# AskelmoottoriV3.net
KiCad netlist of a schematic drawn in EAGLE
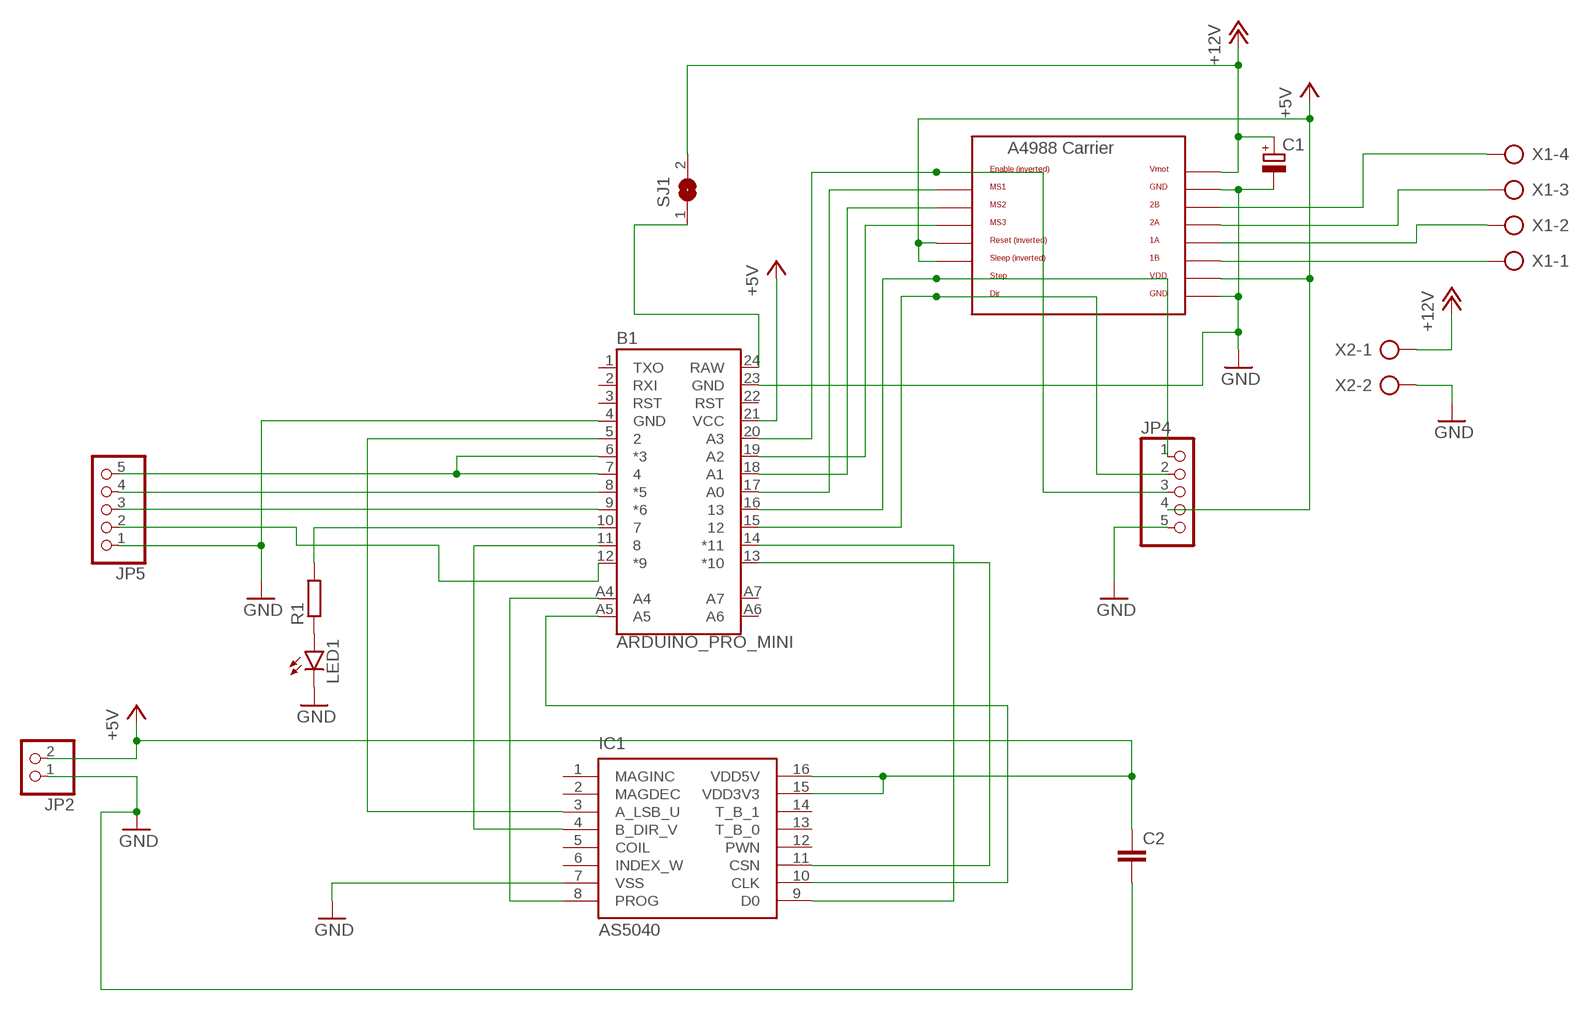
[diagram p0: schematic, sheet 1]

(export (version "E")
  (design (tool "Eeschema 10.0.6"))
  (components
    (comp (ref "B1")
      (value "ARDUINO_PRO_MINI")
      (footprint "eagle-import:ARDUINO_PRO_MINI")
      (libsource (lib "eagle-import") (part "ARDUINO_PRO_MINI"))
    )
    (comp (ref "C1")
      (value "CPOL-EUE5-8.5")
      (footprint "eagle-import:E5-8,5")
      (libsource (lib "eagle-import") (part "CPOL-EUE5-8.5"))
    )
    (comp (ref "C2")
      (value "C-EU025-030X050")
      (footprint "eagle-import:C025-030X050")
      (libsource (lib "eagle-import") (part "C-EU025-030X050"))
    )
    (comp (ref "IC1")
      (value "AS5040")
      (footprint "eagle-import:SSOP16")
      (fields (field (name "MPN") "AS5040ASSU"))
      (libsource (lib "eagle-import") (part "AS5040"))
    )
    (comp (ref "JP2")
      (value "PINHD-1X2")
      (footprint "eagle-import:1X02")
      (libsource (lib "eagle-import") (part "PINHD-1X2"))
    )
    (comp (ref "JP4")
      (value "PINHD-1X5")
      (footprint "eagle-import:1X05")
      (libsource (lib "eagle-import") (part "PINHD-1X5"))
    )
    (comp (ref "JP5")
      (value "PINHD-1X5")
      (footprint "eagle-import:1X05")
      (libsource (lib "eagle-import") (part "PINHD-1X5"))
    )
    (comp (ref "LED1")
      (value "LED3MM")
      (footprint "eagle-import:LED3MM")
      (libsource (lib "eagle-import") (part "LED3MM"))
    )
    (comp (ref "R1")
      (value "R-EU_0207/10")
      (footprint "eagle-import:0207_10")
      (libsource (lib "eagle-import") (part "R-EU_0207/10"))
    )
    (comp (ref "SJ1") (value "SJ") (footprint "eagle-import:SJ") (libsource (lib "eagle-import") (part "SJ")))
    (comp (ref "U$1")
      (value "A4988BREAKOUT")
      (footprint "eagle-import:A4988BREAKOUT")
      (libsource (lib "eagle-import") (part "A4988BREAKOUT"))
    )
    (comp (ref "X1")
      (value "AK300/4")
      (footprint "eagle-import:AK300_4")
      (libsource (lib "eagle-import") (part "AK300/4"))
    )
    (comp (ref "X2")
      (value "AK300/2")
      (footprint "eagle-import:AK300_2")
      (libsource (lib "eagle-import") (part "AK300/2"))
    )
  )
  (nets
    (net (code "1") (name "+5V") (class "Default")
      (node (ref "B1") (pin "21") (pinfunction "VCC_21") (pintype "power_in"))
      (node (ref "C2") (pin "1") (pinfunction "1_1") (pintype "passive"))
      (node (ref "IC1") (pin "15") (pinfunction "VDD3V3_15") (pintype "passive"))
      (node (ref "IC1") (pin "16") (pinfunction "VDD5V_16") (pintype "passive"))
      (node (ref "JP2") (pin "2") (pinfunction "2_2") (pintype "passive"))
      (node (ref "JP4") (pin "4") (pinfunction "4_4") (pintype "passive"))
      (node (ref "U$1") (pin "RST") (pinfunction "RST_RST") (pintype "input"))
      (node (ref "U$1") (pin "SLP") (pinfunction "SLEEP_SLP") (pintype "input"))
      (node (ref "U$1") (pin "VDD") (pinfunction "VDD_VDD") (pintype "power_in"))
    )
    (net (code "2") (name "+12V") (class "Default")
      (node (ref "C1") (pin "+") (pinfunction "+_+") (pintype "passive"))
      (node (ref "SJ1") (pin "2") (pinfunction "2_2") (pintype "passive"))
      (node (ref "U$1") (pin "VMOT") (pinfunction "VMOT_VMOT") (pintype "power_in"))
      (node (ref "X2") (pin "1") (pinfunction "KL_1") (pintype "passive"))
    )
    (net (code "3") (name "GND") (class "Default")
      (node (ref "B1") (pin "23") (pinfunction "GND_23") (pintype "power_in"))
      (node (ref "B1") (pin "4") (pinfunction "GND_4") (pintype "power_in"))
      (node (ref "C1") (pin "-") (pinfunction "-_-") (pintype "passive"))
      (node (ref "C2") (pin "2") (pinfunction "2_2") (pintype "passive"))
      (node (ref "IC1") (pin "7") (pinfunction "VSS_7") (pintype "passive"))
      (node (ref "JP2") (pin "1") (pinfunction "1_1") (pintype "passive"))
      (node (ref "JP4") (pin "5") (pinfunction "5_5") (pintype "passive"))
      (node (ref "JP5") (pin "1") (pinfunction "1_1") (pintype "passive"))
      (node (ref "LED1") (pin "K") (pinfunction "C_K") (pintype "passive"))
      (node (ref "U$1") (pin "GND") (pinfunction "GND_GND") (pintype "power_in"))
      (node (ref "U$1") (pin "GND@0") (pinfunction "GND_GND@0") (pintype "power_in"))
      (node (ref "X2") (pin "2") (pinfunction "KL_2") (pintype "passive"))
    )
    (net (code "4") (name "Net-(B1-*3)") (class "Default")
      (node (ref "B1") (pin "6") (pinfunction "*3_6") (pintype "bidirectional"))
      (node (ref "B1") (pin "7") (pinfunction "4_7") (pintype "bidirectional"))
      (node (ref "JP5") (pin "5") (pinfunction "5_5") (pintype "passive"))
    )
    (net (code "5") (name "Net-(B1-*5)") (class "Default")
      (node (ref "B1") (pin "8") (pinfunction "*5_8") (pintype "bidirectional"))
      (node (ref "JP5") (pin "4") (pinfunction "4_4") (pintype "passive"))
    )
    (net (code "6") (name "Net-(B1-*6)") (class "Default")
      (node (ref "B1") (pin "9") (pinfunction "*6_9") (pintype "bidirectional"))
      (node (ref "JP5") (pin "3") (pinfunction "3_3") (pintype "passive"))
    )
    (net (code "7") (name "Net-(B1-*9)") (class "Default")
      (node (ref "B1") (pin "12") (pinfunction "*9_12") (pintype "bidirectional"))
      (node (ref "JP5") (pin "2") (pinfunction "2_2") (pintype "passive"))
    )
    (net (code "8") (name "Net-(B1-*10)") (class "Default")
      (node (ref "B1") (pin "13") (pinfunction "*10_13") (pintype "bidirectional"))
      (node (ref "IC1") (pin "11") (pinfunction "CSN_11") (pintype "input"))
    )
    (net (code "9") (name "Net-(B1-*11)") (class "Default")
      (node (ref "B1") (pin "14") (pinfunction "*11_14") (pintype "bidirectional"))
      (node (ref "IC1") (pin "9") (pinfunction "D0_9") (pintype "tri_state"))
    )
    (net (code "10") (name "Net-(B1-2)") (class "Default")
      (node (ref "B1") (pin "5") (pinfunction "2_5") (pintype "bidirectional"))
      (node (ref "IC1") (pin "3") (pinfunction "A_LSB_U_3") (pintype "output"))
    )
    (net (code "11") (name "Net-(B1-7)") (class "Default")
      (node (ref "B1") (pin "10") (pinfunction "7_10") (pintype "bidirectional"))
      (node (ref "R1") (pin "2") (pinfunction "2_2") (pintype "passive"))
    )
    (net (code "12") (name "Net-(B1-8)") (class "Default")
      (node (ref "B1") (pin "11") (pinfunction "8_11") (pintype "bidirectional"))
      (node (ref "IC1") (pin "4") (pinfunction "B_DIR_V_4") (pintype "output"))
    )
    (net (code "13") (name "Net-(B1-12)") (class "Default")
      (node (ref "B1") (pin "15") (pinfunction "12_15") (pintype "bidirectional"))
      (node (ref "JP4") (pin "2") (pinfunction "2_2") (pintype "passive"))
      (node (ref "U$1") (pin "DIR") (pinfunction "DIR_DIR") (pintype "input"))
    )
    (net (code "14") (name "Net-(B1-13)") (class "Default")
      (node (ref "B1") (pin "16") (pinfunction "13_16") (pintype "bidirectional"))
      (node (ref "JP4") (pin "1") (pinfunction "1_1") (pintype "passive"))
      (node (ref "U$1") (pin "STEP") (pinfunction "STEP_STEP") (pintype "input"))
    )
    (net (code "15") (name "Net-(B1-A0)") (class "Default")
      (node (ref "B1") (pin "17") (pinfunction "A0_17") (pintype "bidirectional"))
      (node (ref "U$1") (pin "MS1") (pinfunction "MS1_MS1") (pintype "input"))
    )
    (net (code "16") (name "Net-(B1-A1)") (class "Default")
      (node (ref "B1") (pin "18") (pinfunction "A1_18") (pintype "bidirectional"))
      (node (ref "U$1") (pin "MS2") (pinfunction "MS2_MS2") (pintype "input"))
    )
    (net (code "17") (name "Net-(B1-A2)") (class "Default")
      (node (ref "B1") (pin "19") (pinfunction "A2_19") (pintype "bidirectional"))
      (node (ref "U$1") (pin "MS3") (pinfunction "MS3_MS3") (pintype "input"))
    )
    (net (code "18") (name "Net-(B1-A3)") (class "Default")
      (node (ref "B1") (pin "20") (pinfunction "A3_20") (pintype "bidirectional"))
      (node (ref "JP4") (pin "3") (pinfunction "3_3") (pintype "passive"))
      (node (ref "U$1") (pin "EN") (pinfunction "EN_EN") (pintype "input"))
    )
    (net (code "19") (name "Net-(B1-RAW)") (class "Default")
      (node (ref "B1") (pin "24") (pinfunction "RAW_24") (pintype "power_in"))
      (node (ref "SJ1") (pin "1") (pinfunction "1_1") (pintype "passive"))
    )
    (net (code "20") (name "Net-(IC1-CLK)") (class "Default")
      (node (ref "B1") (pin "A5") (pinfunction "A5_A5") (pintype "bidirectional"))
      (node (ref "IC1") (pin "10") (pinfunction "CLK_10") (pintype "input"))
    )
    (net (code "21") (name "Net-(IC1-PROG)") (class "Default")
      (node (ref "B1") (pin "A4") (pinfunction "A4_A4") (pintype "bidirectional"))
      (node (ref "IC1") (pin "8") (pinfunction "PROG_8") (pintype "input"))
    )
    (net (code "22") (name "Net-(LED1-PadA)") (class "Default")
      (node (ref "LED1") (pin "A") (pinfunction "A_A") (pintype "passive"))
      (node (ref "R1") (pin "1") (pinfunction "1_1") (pintype "passive"))
    )
    (net (code "23") (name "Net-(X1A-KL)") (class "Default")
      (node (ref "U$1") (pin "1B") (pinfunction "1B_1B") (pintype "output"))
      (node (ref "X1") (pin "1") (pinfunction "KL_1") (pintype "passive"))
    )
    (net (code "24") (name "Net-(X1B-KL)") (class "Default")
      (node (ref "U$1") (pin "1A") (pinfunction "1A_1A") (pintype "output"))
      (node (ref "X1") (pin "2") (pinfunction "KL_2") (pintype "passive"))
    )
    (net (code "25") (name "Net-(X1C-KL)") (class "Default")
      (node (ref "U$1") (pin "2A") (pinfunction "2A_2A") (pintype "output"))
      (node (ref "X1") (pin "3") (pinfunction "KL_3") (pintype "passive"))
    )
    (net (code "26") (name "Net-(X1D-KL)") (class "Default")
      (node (ref "U$1") (pin "2B") (pinfunction "2B_2B") (pintype "output"))
      (node (ref "X1") (pin "4") (pinfunction "KL_4") (pintype "passive"))
    )
    (net (code "27") (name "unconnected-(B1-PadA6)") (class "Default")
      (node (ref "B1") (pin "A6") (pinfunction "A6_A6") (pintype "bidirectional"))
    )
    (net (code "28") (name "unconnected-(B1-PadA7)") (class "Default")
      (node (ref "B1") (pin "A7") (pinfunction "A7_A7") (pintype "bidirectional"))
    )
    (net (code "29") (name "unconnected-(B1-RST-Pad3)") (class "Default")
      (node (ref "B1") (pin "3") (pinfunction "RST_3") (pintype "bidirectional"))
    )
    (net (code "30") (name "unconnected-(B1-RST-Pad22)") (class "Default")
      (node (ref "B1") (pin "22") (pinfunction "RST_22") (pintype "bidirectional"))
    )
    (net (code "31") (name "unconnected-(B1-RXI-Pad2)") (class "Default")
      (node (ref "B1") (pin "2") (pinfunction "RXI_2") (pintype "bidirectional"))
    )
    (net (code "32") (name "unconnected-(B1-TXO-Pad1)") (class "Default")
      (node (ref "B1") (pin "1") (pinfunction "TXO_1") (pintype "bidirectional"))
    )
    (net (code "33") (name "unconnected-(IC1-COIL-Pad5)") (class "Default")
      (node (ref "IC1") (pin "5") (pinfunction "COIL_5") (pintype "no_connect"))
    )
    (net (code "34") (name "unconnected-(IC1-INDEX_W-Pad6)") (class "Default")
      (node (ref "IC1") (pin "6") (pinfunction "INDEX_W_6") (pintype "output"))
    )
    (net (code "35") (name "unconnected-(IC1-MAGDEC-Pad2)") (class "Default")
      (node (ref "IC1") (pin "2") (pinfunction "MAGDEC_2") (pintype "tri_state"))
    )
    (net (code "36") (name "unconnected-(IC1-MAGINC-Pad1)") (class "Default")
      (node (ref "IC1") (pin "1") (pinfunction "MAGINC_1") (pintype "tri_state"))
    )
    (net (code "37") (name "unconnected-(IC1-PWN-Pad12)") (class "Default")
      (node (ref "IC1") (pin "12") (pinfunction "PWN_12") (pintype "passive"))
    )
    (net (code "38") (name "unconnected-(IC1-T_B_0-Pad13)") (class "Default")
      (node (ref "IC1") (pin "13") (pinfunction "T_B_0_13") (pintype "no_connect"))
    )
    (net (code "39") (name "unconnected-(IC1-T_B_1-Pad14)") (class "Default")
      (node (ref "IC1") (pin "14") (pinfunction "T_B_1_14") (pintype "no_connect"))
    )
  )
)
